# 34063.net
KiCad netlist of a schematic drawn in EAGLE
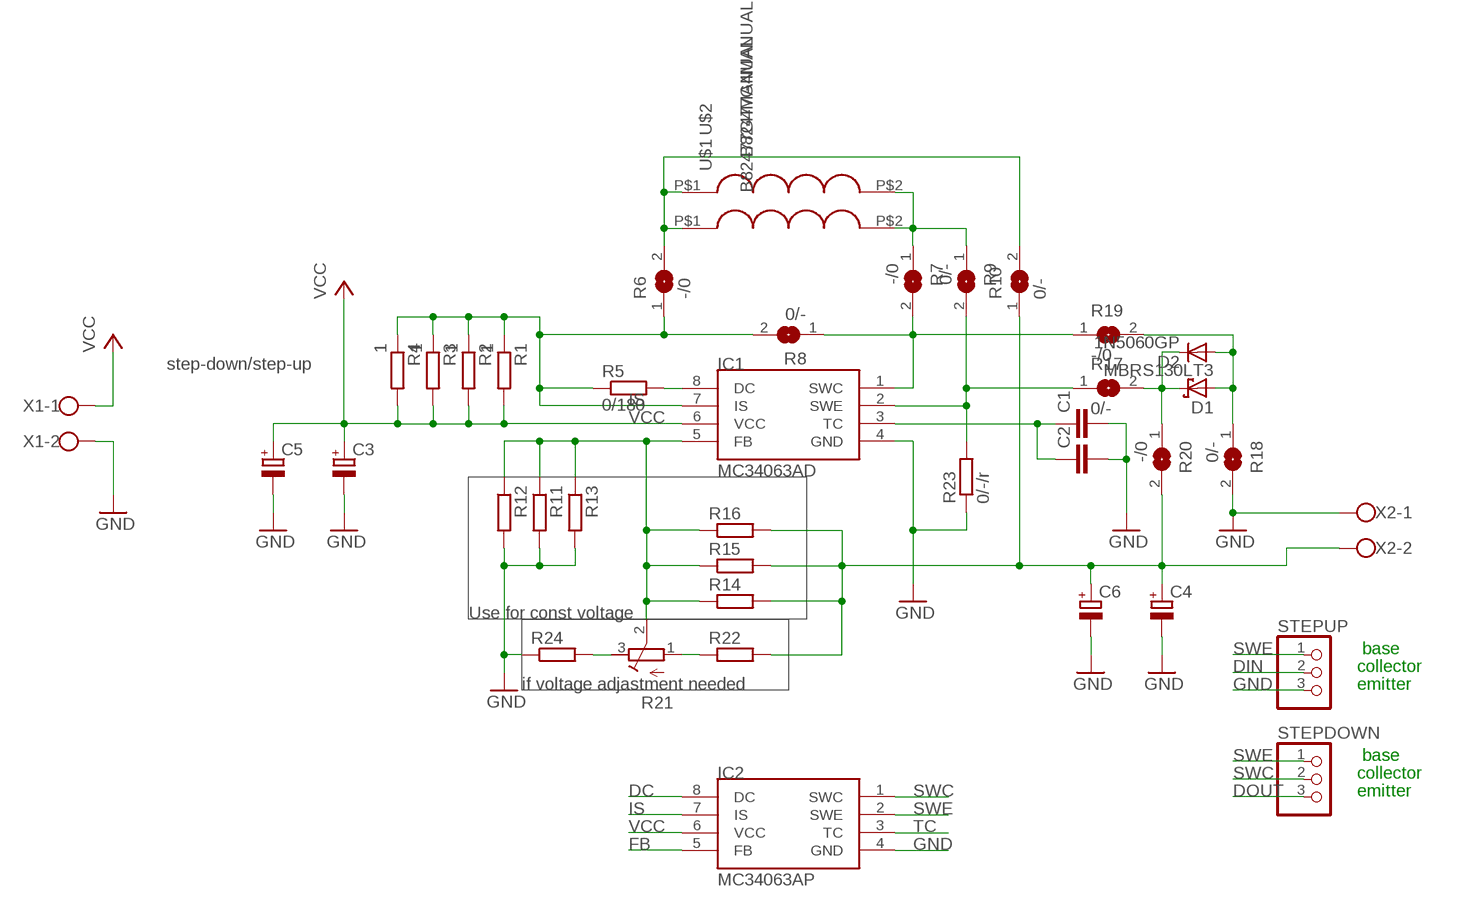
[diagram p0: schematic, sheet 1]

(export (version "E")
  (design (tool "Eeschema 10.0.6"))
  (components
    (comp (ref "C1")
      (value "C-EUC0805")
      (footprint "eagle-import:C0805")
      (libsource (lib "eagle-import") (part "C-EUC0805"))
    )
    (comp (ref "C2")
      (value "C-EU050-024X044")
      (footprint "eagle-import:C050-024X044")
      (libsource (lib "eagle-import") (part "C-EU050-024X044"))
    )
    (comp (ref "C3")
      (value "CPOL-EUE5-13")
      (footprint "eagle-import:E5-13")
      (libsource (lib "eagle-import") (part "CPOL-EUE5-13"))
    )
    (comp (ref "C4")
      (value "CPOL-EUE5-13")
      (footprint "eagle-import:E5-13")
      (libsource (lib "eagle-import") (part "CPOL-EUE5-13"))
    )
    (comp (ref "C5")
      (value "CPOL-EUE2.5-7")
      (footprint "eagle-import:E2,5-7")
      (libsource (lib "eagle-import") (part "CPOL-EUE2.5-7"))
    )
    (comp (ref "C6")
      (value "CPOL-EUE2.5-7")
      (footprint "eagle-import:E2,5-7")
      (libsource (lib "eagle-import") (part "CPOL-EUE2.5-7"))
    )
    (comp (ref "D1")
      (value "MBRS130LT3")
      (footprint "eagle-import:SMB")
      (libsource (lib "eagle-import") (part "MBRS130LT3"))
    )
    (comp (ref "D2")
      (value "1N5060GP")
      (footprint "eagle-import:DO15-12")
      (libsource (lib "eagle-import") (part "1N5060GP"))
    )
    (comp (ref "IC1")
      (value "MC34063AD")
      (footprint "eagle-import:SOIC8")
      (libsource (lib "eagle-import") (part "MC34063AD"))
    )
    (comp (ref "IC2")
      (value "MC34063AP")
      (footprint "eagle-import:DIL08")
      (libsource (lib "eagle-import") (part "MC34063AP"))
    )
    (comp (ref "R1")
      (value "1")
      (footprint "eagle-import:M1206")
      (libsource (lib "eagle-import") (part "R-EU_M1206"))
    )
    (comp (ref "R2")
      (value "1")
      (footprint "eagle-import:M1206")
      (libsource (lib "eagle-import") (part "R-EU_M1206"))
    )
    (comp (ref "R3")
      (value "1")
      (footprint "eagle-import:M1206")
      (libsource (lib "eagle-import") (part "R-EU_M1206"))
    )
    (comp (ref "R4")
      (value "1")
      (footprint "eagle-import:M1206")
      (libsource (lib "eagle-import") (part "R-EU_M1206"))
    )
    (comp (ref "R5")
      (value "0/180")
      (footprint "eagle-import:M0805")
      (libsource (lib "eagle-import") (part "R-EU_M0805"))
    )
    (comp (ref "R6") (value "-/0") (footprint "eagle-import:SJ") (libsource (lib "eagle-import") (part "SJ")))
    (comp (ref "R7") (value "-/0") (footprint "eagle-import:SJ") (libsource (lib "eagle-import") (part "SJ")))
    (comp (ref "R8") (value "0/-") (footprint "eagle-import:SJ") (libsource (lib "eagle-import") (part "SJ")))
    (comp (ref "R9") (value "0/-") (footprint "eagle-import:SJ") (libsource (lib "eagle-import") (part "SJ")))
    (comp (ref "R10")
      (value "0/-")
      (footprint "eagle-import:SJ")
      (libsource (lib "eagle-import") (part "SJ"))
    )
    (comp (ref "R11")
      (value "R-EU_R0805")
      (footprint "eagle-import:R0805")
      (libsource (lib "eagle-import") (part "R-EU_R0805"))
    )
    (comp (ref "R12")
      (value "R-EU_R0805")
      (footprint "eagle-import:R0805")
      (libsource (lib "eagle-import") (part "R-EU_R0805"))
    )
    (comp (ref "R13")
      (value "R-EU_0204/2V")
      (footprint "eagle-import:0204V")
      (libsource (lib "eagle-import") (part "R-EU_0204/2V"))
    )
    (comp (ref "R14")
      (value "R-EU_R0805")
      (footprint "eagle-import:R0805")
      (libsource (lib "eagle-import") (part "R-EU_R0805"))
    )
    (comp (ref "R15")
      (value "R-EU_R0805")
      (footprint "eagle-import:R0805")
      (libsource (lib "eagle-import") (part "R-EU_R0805"))
    )
    (comp (ref "R16")
      (value "R-EU_0204/2V")
      (footprint "eagle-import:0204V")
      (libsource (lib "eagle-import") (part "R-EU_0204/2V"))
    )
    (comp (ref "R17")
      (value "0/-")
      (footprint "eagle-import:SJ")
      (libsource (lib "eagle-import") (part "SJ"))
    )
    (comp (ref "R18")
      (value "0/-")
      (footprint "eagle-import:SJ")
      (libsource (lib "eagle-import") (part "SJ"))
    )
    (comp (ref "R19")
      (value "-/0")
      (footprint "eagle-import:SJ")
      (libsource (lib "eagle-import") (part "SJ"))
    )
    (comp (ref "R20")
      (value "-/0")
      (footprint "eagle-import:SJ")
      (libsource (lib "eagle-import") (part "SJ"))
    )
    (comp (ref "R21")
      (value "R-TRIMM64W")
      (footprint "eagle-import:RTRIM64W")
      (libsource (lib "eagle-import") (part "R-TRIMM64W"))
    )
    (comp (ref "R22")
      (value "R-EU_R0805")
      (footprint "eagle-import:R0805")
      (libsource (lib "eagle-import") (part "R-EU_R0805"))
    )
    (comp (ref "R23")
      (value "0/-/r")
      (footprint "eagle-import:R0805")
      (libsource (lib "eagle-import") (part "R-EU_R0805"))
    )
    (comp (ref "R24")
      (value "R-EU_R0805")
      (footprint "eagle-import:R0805")
      (libsource (lib "eagle-import") (part "R-EU_R0805"))
    )
    (comp (ref "STEPDOWN")
      (value "PINHD-1X3")
      (footprint "eagle-import:1X03")
      (libsource (lib "eagle-import") (part "PINHD-1X3"))
    )
    (comp (ref "STEPUP")
      (value "PINHD-1X3")
      (footprint "eagle-import:1X03")
      (libsource (lib "eagle-import") (part "PINHD-1X3"))
    )
    (comp (ref "U$1")
      (value "B82477G4MANUAL")
      (footprint "eagle-import:B82477G4_MANUAL")
      (libsource (lib "eagle-import") (part "B82477G4MANUAL"))
    )
    (comp (ref "U$2")
      (value "B82477G4MANUAL")
      (footprint "eagle-import:B82477G4_MANUAL")
      (libsource (lib "eagle-import") (part "B82477G4MANUAL"))
    )
    (comp (ref "X1")
      (value "W237-102")
      (footprint "eagle-import:W237-102")
      (fields (field (name "MPN") "237-102"))
      (libsource (lib "eagle-import") (part "W237-102"))
    )
    (comp (ref "X2")
      (value "W237-102")
      (footprint "eagle-import:W237-102")
      (fields (field (name "MPN") "237-102"))
      (libsource (lib "eagle-import") (part "W237-102"))
    )
  )
  (nets
    (net (code "1") (name "/DC") (class "Default")
      (node (ref "IC1") (pin "8") (pinfunction "DC_8") (pintype "passive"))
      (node (ref "IC2") (pin "8") (pinfunction "DC_8") (pintype "passive"))
      (node (ref "R5") (pin "2") (pinfunction "2_2") (pintype "passive"))
    )
    (net (code "2") (name "/DIN") (class "Default")
      (node (ref "D1") (pin "A") (pinfunction "A_A") (pintype "passive"))
      (node (ref "D2") (pin "A") (pinfunction "A_A") (pintype "passive"))
      (node (ref "R18") (pin "1") (pinfunction "1_1") (pintype "passive"))
      (node (ref "R19") (pin "2") (pinfunction "2_2") (pintype "passive"))
      (node (ref "STEPUP") (pin "2") (pinfunction "2_2") (pintype "passive"))
    )
    (net (code "3") (name "/DOUT") (class "Default")
      (node (ref "D1") (pin "C") (pinfunction "C_C") (pintype "passive"))
      (node (ref "D2") (pin "C") (pinfunction "C_C") (pintype "passive"))
      (node (ref "R17") (pin "2") (pinfunction "2_2") (pintype "passive"))
      (node (ref "R20") (pin "1") (pinfunction "1_1") (pintype "passive"))
      (node (ref "STEPDOWN") (pin "3") (pinfunction "3_3") (pintype "passive"))
    )
    (net (code "4") (name "/FB") (class "Default")
      (node (ref "IC1") (pin "5") (pinfunction "FB_5") (pintype "passive"))
      (node (ref "IC2") (pin "5") (pinfunction "FB_5") (pintype "passive"))
      (node (ref "R11") (pin "1") (pinfunction "1_1") (pintype "passive"))
      (node (ref "R12") (pin "1") (pinfunction "1_1") (pintype "passive"))
      (node (ref "R13") (pin "1") (pinfunction "1_1") (pintype "passive"))
      (node (ref "R14") (pin "1") (pinfunction "1_1") (pintype "passive"))
      (node (ref "R15") (pin "1") (pinfunction "1_1") (pintype "passive"))
      (node (ref "R16") (pin "1") (pinfunction "1_1") (pintype "passive"))
      (node (ref "R21") (pin "2") (pinfunction "S_2") (pintype "passive"))
    )
    (net (code "5") (name "/IS") (class "Default")
      (node (ref "IC1") (pin "7") (pinfunction "IS_7") (pintype "passive"))
      (node (ref "IC2") (pin "7") (pinfunction "IS_7") (pintype "passive"))
      (node (ref "R1") (pin "1") (pinfunction "1_1") (pintype "passive"))
      (node (ref "R2") (pin "1") (pinfunction "1_1") (pintype "passive"))
      (node (ref "R3") (pin "1") (pinfunction "1_1") (pintype "passive"))
      (node (ref "R4") (pin "1") (pinfunction "1_1") (pintype "passive"))
      (node (ref "R5") (pin "1") (pinfunction "1_1") (pintype "passive"))
      (node (ref "R6") (pin "1") (pinfunction "1_1") (pintype "passive"))
      (node (ref "R8") (pin "2") (pinfunction "2_2") (pintype "passive"))
    )
    (net (code "6") (name "/SWC") (class "Default")
      (node (ref "IC1") (pin "1") (pinfunction "SWC_1") (pintype "passive"))
      (node (ref "IC2") (pin "1") (pinfunction "SWC_1") (pintype "passive"))
      (node (ref "R19") (pin "1") (pinfunction "1_1") (pintype "passive"))
      (node (ref "R7") (pin "2") (pinfunction "2_2") (pintype "passive"))
      (node (ref "R8") (pin "1") (pinfunction "1_1") (pintype "passive"))
      (node (ref "STEPDOWN") (pin "2") (pinfunction "2_2") (pintype "passive"))
    )
    (net (code "7") (name "/SWE") (class "Default")
      (node (ref "IC1") (pin "2") (pinfunction "SWE_2") (pintype "passive"))
      (node (ref "IC2") (pin "2") (pinfunction "SWE_2") (pintype "passive"))
      (node (ref "R17") (pin "1") (pinfunction "1_1") (pintype "passive"))
      (node (ref "R23") (pin "2") (pinfunction "2_2") (pintype "passive"))
      (node (ref "R9") (pin "2") (pinfunction "2_2") (pintype "passive"))
      (node (ref "STEPDOWN") (pin "1") (pinfunction "1_1") (pintype "passive"))
      (node (ref "STEPUP") (pin "1") (pinfunction "1_1") (pintype "passive"))
    )
    (net (code "8") (name "/TC") (class "Default")
      (node (ref "C1") (pin "1") (pinfunction "1_1") (pintype "passive"))
      (node (ref "C2") (pin "1") (pinfunction "1_1") (pintype "passive"))
      (node (ref "IC1") (pin "3") (pinfunction "TC_3") (pintype "passive"))
      (node (ref "IC2") (pin "3") (pinfunction "TC_3") (pintype "passive"))
    )
    (net (code "9") (name "GND") (class "Default")
      (node (ref "C1") (pin "2") (pinfunction "2_2") (pintype "passive"))
      (node (ref "C2") (pin "2") (pinfunction "2_2") (pintype "passive"))
      (node (ref "C3") (pin "-") (pinfunction "-_-") (pintype "passive"))
      (node (ref "C4") (pin "-") (pinfunction "-_-") (pintype "passive"))
      (node (ref "C5") (pin "-") (pinfunction "-_-") (pintype "passive"))
      (node (ref "C6") (pin "-") (pinfunction "-_-") (pintype "passive"))
      (node (ref "IC1") (pin "4") (pinfunction "GND_4") (pintype "passive"))
      (node (ref "IC2") (pin "4") (pinfunction "GND_4") (pintype "passive"))
      (node (ref "R11") (pin "2") (pinfunction "2_2") (pintype "passive"))
      (node (ref "R12") (pin "2") (pinfunction "2_2") (pintype "passive"))
      (node (ref "R13") (pin "2") (pinfunction "2_2") (pintype "passive"))
      (node (ref "R18") (pin "2") (pinfunction "2_2") (pintype "passive"))
      (node (ref "R23") (pin "1") (pinfunction "1_1") (pintype "passive"))
      (node (ref "R24") (pin "1") (pinfunction "1_1") (pintype "passive"))
      (node (ref "STEPUP") (pin "3") (pinfunction "3_3") (pintype "passive"))
      (node (ref "X1") (pin "2") (pinfunction "KL_2") (pintype "passive"))
      (node (ref "X2") (pin "1") (pinfunction "KL_1") (pintype "passive"))
    )
    (net (code "10") (name "Net-(R7-Pad1)") (class "Default")
      (node (ref "R7") (pin "1") (pinfunction "1_1") (pintype "passive"))
      (node (ref "R9") (pin "1") (pinfunction "1_1") (pintype "passive"))
      (node (ref "U$1") (pin "P$2") (pinfunction "P$2_P$2") (pintype "bidirectional"))
      (node (ref "U$2") (pin "P$2") (pinfunction "P$2_P$2") (pintype "bidirectional"))
    )
    (net (code "11") (name "Net-(R10-Pad2)") (class "Default")
      (node (ref "R10") (pin "2") (pinfunction "2_2") (pintype "passive"))
      (node (ref "R6") (pin "2") (pinfunction "2_2") (pintype "passive"))
      (node (ref "U$1") (pin "P$1") (pinfunction "P$1_P$1") (pintype "bidirectional"))
      (node (ref "U$2") (pin "P$1") (pinfunction "P$1_P$1") (pintype "bidirectional"))
    )
    (net (code "12") (name "Net-(R21-A)") (class "Default")
      (node (ref "R21") (pin "1") (pinfunction "A_1") (pintype "passive"))
      (node (ref "R22") (pin "1") (pinfunction "1_1") (pintype "passive"))
    )
    (net (code "13") (name "Net-(R21-E)") (class "Default")
      (node (ref "R21") (pin "3") (pinfunction "E_3") (pintype "passive"))
      (node (ref "R24") (pin "2") (pinfunction "2_2") (pintype "passive"))
    )
    (net (code "14") (name "Net-(X2B-KL)") (class "Default")
      (node (ref "C4") (pin "+") (pinfunction "+_+") (pintype "passive"))
      (node (ref "C6") (pin "+") (pinfunction "+_+") (pintype "passive"))
      (node (ref "R10") (pin "1") (pinfunction "1_1") (pintype "passive"))
      (node (ref "R14") (pin "2") (pinfunction "2_2") (pintype "passive"))
      (node (ref "R15") (pin "2") (pinfunction "2_2") (pintype "passive"))
      (node (ref "R16") (pin "2") (pinfunction "2_2") (pintype "passive"))
      (node (ref "R20") (pin "2") (pinfunction "2_2") (pintype "passive"))
      (node (ref "R22") (pin "2") (pinfunction "2_2") (pintype "passive"))
      (node (ref "X2") (pin "2") (pinfunction "KL_2") (pintype "passive"))
    )
    (net (code "15") (name "VCC") (class "Default")
      (node (ref "C3") (pin "+") (pinfunction "+_+") (pintype "passive"))
      (node (ref "C5") (pin "+") (pinfunction "+_+") (pintype "passive"))
      (node (ref "IC1") (pin "6") (pinfunction "VCC_6") (pintype "passive"))
      (node (ref "IC2") (pin "6") (pinfunction "VCC_6") (pintype "passive"))
      (node (ref "R1") (pin "2") (pinfunction "2_2") (pintype "passive"))
      (node (ref "R2") (pin "2") (pinfunction "2_2") (pintype "passive"))
      (node (ref "R3") (pin "2") (pinfunction "2_2") (pintype "passive"))
      (node (ref "R4") (pin "2") (pinfunction "2_2") (pintype "passive"))
      (node (ref "X1") (pin "1") (pinfunction "KL_1") (pintype "passive"))
    )
  )
)
